# L-Stick_sheet5_power_supply.net
KiCad netlist of a schematic drawn in Altium Designer
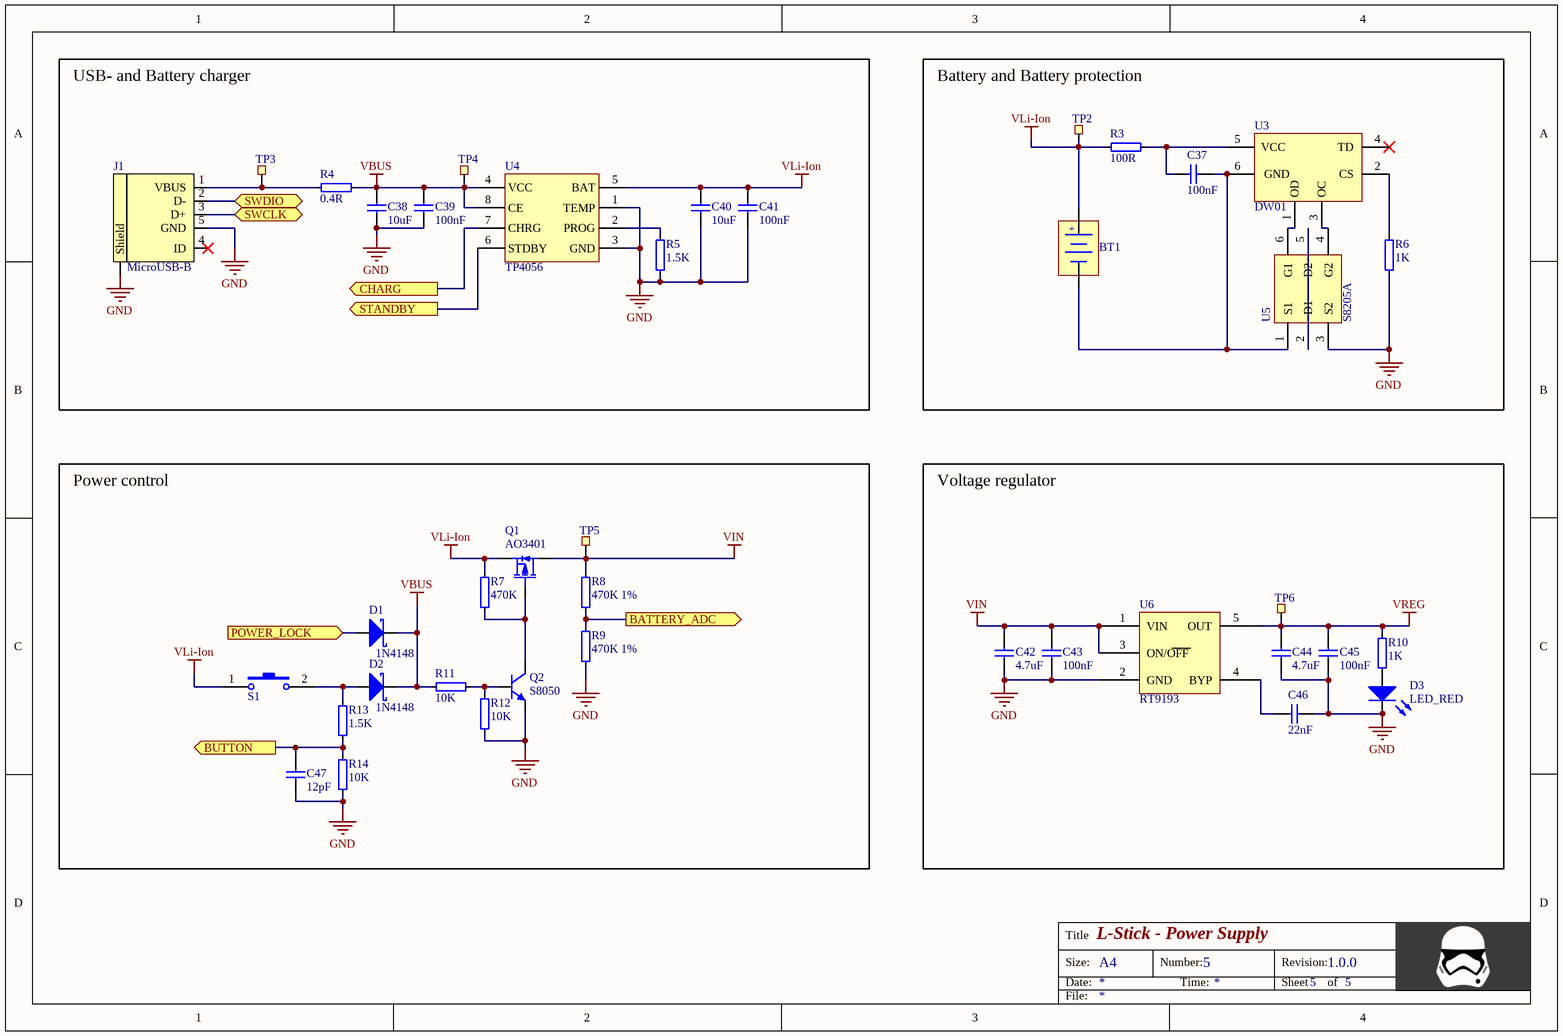
[diagram p0: L-Stick_sheet5_power_supply.SchDoc]

(export (version "E")
  (design (tool "Eeschema 10.0.6"))
  (components
    (comp (ref "BT1")
      (value "XH2.54_2PIN")
      (footprint "XH2.54_2PIN")
      (description "Multicell Battery Base")
      (libsource (lib "L-Stick") (part "Battery"))
    )
    (comp (ref "C37")
      (value "100nF")
      (footprint "0402C")
      (description "Capacitor")
      (libsource (lib "L-Stick") (part "CAP_0402"))
    )
    (comp (ref "C38")
      (value "10uF")
      (footprint "0603C")
      (description "Capacitor")
      (libsource (lib "L-Stick") (part "CAP_0603"))
    )
    (comp (ref "C39")
      (value "100nF")
      (footprint "0402C")
      (description "Capacitor")
      (libsource (lib "L-Stick") (part "CAP_0402"))
    )
    (comp (ref "C40")
      (value "10uF")
      (footprint "0603C")
      (description "Capacitor")
      (libsource (lib "L-Stick") (part "CAP_0603"))
    )
    (comp (ref "C41")
      (value "100nF")
      (footprint "0402C")
      (description "Capacitor")
      (libsource (lib "L-Stick") (part "CAP_0402"))
    )
    (comp (ref "C42")
      (value "4.7uF")
      (footprint "0603C")
      (description "Capacitor")
      (libsource (lib "L-Stick") (part "CAP_0603"))
    )
    (comp (ref "C43")
      (value "100nF")
      (footprint "0402C")
      (description "Capacitor")
      (libsource (lib "L-Stick") (part "CAP_0402"))
    )
    (comp (ref "C44")
      (value "4.7uF")
      (footprint "0603C")
      (description "Capacitor")
      (libsource (lib "L-Stick") (part "CAP_0603"))
    )
    (comp (ref "C45")
      (value "100nF")
      (footprint "0402C")
      (description "Capacitor")
      (libsource (lib "L-Stick") (part "CAP_0402"))
    )
    (comp (ref "C46")
      (value "22nF")
      (footprint "0402C")
      (description "Capacitor")
      (libsource (lib "L-Stick") (part "CAP_0402"))
    )
    (comp (ref "C47")
      (value "12pF")
      (footprint "0402C")
      (description "Capacitor")
      (libsource (lib "L-Stick") (part "CAP_0402"))
    )
    (comp (ref "D1")
      (value "1N4148")
      (footprint "SOD-523")
      (description "Diode Schottky")
      (libsource (lib "L-Stick") (part "Diode Schottky"))
    )
    (comp (ref "D2")
      (value "1N4148")
      (footprint "SOD-523")
      (description "Diode Schottky")
      (libsource (lib "L-Stick") (part "Diode Schottky"))
    )
    (comp (ref "D3")
      (value "LED_RED")
      (footprint "LED_RED_0603")
      (libsource (lib "L-Stick") (part "LED_RED"))
    )
    (comp (ref "J1")
      (value "MicroUSB-B")
      (footprint "USB-Micro")
      (description "MicroUSB-B-SMT")
      (libsource (lib "L-Stick") (part "MiniUSB-AB-SMT"))
    )
    (comp (ref "Q1")
      (value "AO3401")
      (footprint "SOT-23A")
      (description "P-MOS, AO3401, P-Channel MOSFET")
      (libsource (lib "L-Stick") (part "MOSFET-P"))
    )
    (comp (ref "Q2")
      (value "S8050")
      (footprint "SOT-23A")
      (description "NPN, S8050, NPN Bipolar Transistor")
      (libsource (lib "L-Stick") (part "NPN"))
    )
    (comp (ref "R3")
      (value "100R")
      (footprint "0402R")
      (description "Resistor")
      (libsource (lib "L-Stick") (part "RES_0402"))
    )
    (comp (ref "R4")
      (value "0.4R")
      (footprint "1206R")
      (description "Resistor")
      (libsource (lib "L-Stick") (part "RES_1206"))
    )
    (comp (ref "R5")
      (value "1.5K")
      (footprint "0402R")
      (description "Resistor")
      (libsource (lib "L-Stick") (part "RES_0402"))
    )
    (comp (ref "R6")
      (value "1K")
      (footprint "0402R")
      (description "Resistor")
      (libsource (lib "L-Stick") (part "RES_0402"))
    )
    (comp (ref "R7")
      (value "470K")
      (footprint "0402R")
      (description "Resistor")
      (libsource (lib "L-Stick") (part "RES_0402"))
    )
    (comp (ref "R8")
      (value "470K 1%")
      (footprint "0402R")
      (description "Resistor")
      (libsource (lib "L-Stick") (part "RES_0402"))
    )
    (comp (ref "R9")
      (value "470K 1%")
      (footprint "0402R")
      (description "Resistor")
      (libsource (lib "L-Stick") (part "RES_0402"))
    )
    (comp (ref "R10")
      (value "1K")
      (footprint "0402R")
      (description "Resistor")
      (libsource (lib "L-Stick") (part "RES_0402"))
    )
    (comp (ref "R11")
      (value "10K")
      (footprint "0402R")
      (description "Resistor")
      (libsource (lib "L-Stick") (part "RES_0402"))
    )
    (comp (ref "R12")
      (value "10K")
      (footprint "0402R")
      (description "Resistor")
      (libsource (lib "L-Stick") (part "RES_0402"))
    )
    (comp (ref "R13")
      (value "1.5K")
      (footprint "0402R")
      (description "Resistor")
      (libsource (lib "L-Stick") (part "RES_0402"))
    )
    (comp (ref "R14")
      (value "10K")
      (footprint "0402R")
      (description "Resistor")
      (libsource (lib "L-Stick") (part "RES_0402"))
    )
    (comp (ref "S1") (value "Side Button") (footprint "SW_SIDE") (libsource (lib "L-Stick") (part "SW-PB")))
    (comp (ref "TP2")
      (value "Ø1.5mm,SMD")
      (footprint "TP_SMD")
      (description "1.0mm circular SMD testpad")
      (libsource (lib "L-Stick") (part "TP_SMD_Ø1.0MM"))
    )
    (comp (ref "TP3")
      (value "Ø1.5mm,SMD")
      (footprint "TP_SMD")
      (description "1.0mm circular SMD testpad")
      (libsource (lib "L-Stick") (part "TP_SMD_Ø1.0MM"))
    )
    (comp (ref "TP4")
      (value "Ø1.5mm,SMD")
      (footprint "TP_SMD")
      (description "1.0mm circular SMD testpad")
      (libsource (lib "L-Stick") (part "TP_SMD_Ø1.0MM"))
    )
    (comp (ref "TP5")
      (value "Ø1.5mm,SMD")
      (footprint "TP_SMD")
      (description "1.0mm circular SMD testpad")
      (libsource (lib "L-Stick") (part "TP_SMD_Ø1.0MM"))
    )
    (comp (ref "TP6")
      (value "Ø1.5mm,SMD")
      (footprint "TP_SMD")
      (description "1.0mm circular SMD testpad")
      (libsource (lib "L-Stick") (part "TP_SMD_Ø1.0MM"))
    )
    (comp (ref "U3")
      (value "DW01")
      (footprint "SOT23-6")
      (description "Chip, DW01, Battery Protection IC")
      (libsource (lib "L-Stick") (part "DW01"))
    )
    (comp (ref "U4")
      (value "TP4056")
      (footprint "SOIC8E")
      (description "Chip, TP4056, Battery charging chip")
      (libsource (lib "L-Stick") (part "TP4056"))
    )
    (comp (ref "U5")
      (value "S8205A")
      (footprint "SOT23-6")
      (description "Chip, S8205A")
      (libsource (lib "L-Stick") (part "S8205A"))
    )
    (comp (ref "U6")
      (value "RT9193")
      (footprint "SOT23-5")
      (description "Chip, RT9193, LDO Regulator")
      (libsource (lib "L-Stick") (part "RT9193"))
    )
  )
  (nets
    (net (code "1") (name "/BATTERY_ADC") (class "Default")
      (node (ref "R8") (pin "2") (pinfunction "2_2") (pintype "passive"))
      (node (ref "R9") (pin "1") (pinfunction "1_1") (pintype "passive"))
    )
    (net (code "2") (name "/BUTTON") (class "Default")
      (node (ref "C47") (pin "2") (pinfunction "2_2") (pintype "passive"))
      (node (ref "R13") (pin "1") (pinfunction "1_1") (pintype "passive"))
      (node (ref "R14") (pin "2") (pinfunction "2_2") (pintype "passive"))
    )
    (net (code "3") (name "/CHARG") (class "Default")
      (node (ref "U4") (pin "7") (pinfunction "CHRG_7") (pintype "passive"))
    )
    (net (code "4") (name "/POWER_LOCK") (class "Default")
      (node (ref "D1") (pin "1") (pinfunction "A_1") (pintype "passive"))
    )
    (net (code "5") (name "/STANDBY") (class "Default")
      (node (ref "U4") (pin "6") (pinfunction "STDBY_6") (pintype "passive"))
    )
    (net (code "6") (name "/SWCLK") (class "Default")
      (node (ref "J1") (pin "3") (pinfunction "D+_3") (pintype "passive"))
    )
    (net (code "7") (name "/SWDIO") (class "Default")
      (node (ref "J1") (pin "2") (pinfunction "D-_2") (pintype "passive"))
    )
    (net (code "8") (name "GND") (class "Default")
      (node (ref "C38") (pin "1") (pinfunction "1_1") (pintype "passive"))
      (node (ref "C39") (pin "1") (pinfunction "1_1") (pintype "passive"))
      (node (ref "C40") (pin "1") (pinfunction "1_1") (pintype "passive"))
      (node (ref "C41") (pin "1") (pinfunction "1_1") (pintype "passive"))
      (node (ref "C42") (pin "1") (pinfunction "1_1") (pintype "passive"))
      (node (ref "C43") (pin "1") (pinfunction "1_1") (pintype "passive"))
      (node (ref "C44") (pin "1") (pinfunction "1_1") (pintype "passive"))
      (node (ref "C45") (pin "1") (pinfunction "1_1") (pintype "passive"))
      (node (ref "C46") (pin "2") (pinfunction "2_2") (pintype "passive"))
      (node (ref "C47") (pin "1") (pinfunction "1_1") (pintype "passive"))
      (node (ref "D3") (pin "2") (pinfunction "K_2") (pintype "passive"))
      (node (ref "J1") (pin "5") (pinfunction "GND_5") (pintype "power_in"))
      (node (ref "J1") (pin "6") (pinfunction "Shield_6") (pintype "power_in"))
      (node (ref "Q2") (pin "2") (pinfunction "E_2") (pintype "passive"))
      (node (ref "R12") (pin "2") (pinfunction "2_2") (pintype "passive"))
      (node (ref "R14") (pin "1") (pinfunction "1_1") (pintype "passive"))
      (node (ref "R5") (pin "1") (pinfunction "1_1") (pintype "passive"))
      (node (ref "R6") (pin "1") (pinfunction "1_1") (pintype "passive"))
      (node (ref "R9") (pin "2") (pinfunction "2_2") (pintype "passive"))
      (node (ref "U4") (pin "1") (pinfunction "TEMP_1") (pintype "passive"))
      (node (ref "U4") (pin "3") (pinfunction "GND_3") (pintype "passive"))
      (node (ref "U5") (pin "3") (pinfunction "S2_3") (pintype "passive"))
      (node (ref "U6") (pin "2") (pinfunction "GND_2") (pintype "passive"))
    )
    (net (code "9") (name "Net-(BT1--)") (class "Default")
      (node (ref "BT1") (pin "2") (pinfunction "-_2") (pintype "passive"))
      (node (ref "C37") (pin "2") (pinfunction "2_2") (pintype "passive"))
      (node (ref "U3") (pin "6") (pinfunction "GND_6") (pintype "passive"))
      (node (ref "U5") (pin "1") (pinfunction "S1_1") (pintype "passive"))
    )
    (net (code "10") (name "Net-(D2-A)") (class "Default")
      (node (ref "D2") (pin "1") (pinfunction "A_1") (pintype "passive"))
      (node (ref "R13") (pin "2") (pinfunction "2_2") (pintype "passive"))
      (node (ref "S1") (pin "2") (pinfunction "2_2") (pintype "passive"))
    )
    (net (code "11") (name "Net-(D3-A)") (class "Default")
      (node (ref "D3") (pin "1") (pinfunction "A_1") (pintype "passive"))
      (node (ref "R10") (pin "1") (pinfunction "1_1") (pintype "passive"))
    )
    (net (code "12") (name "Net-(J1-VBUS)") (class "Default")
      (node (ref "J1") (pin "1") (pinfunction "VBUS_1") (pintype "power_in"))
      (node (ref "R4") (pin "1") (pinfunction "1_1") (pintype "passive"))
      (node (ref "TP3") (pin "1") (pinfunction "1_1") (pintype "passive"))
    )
    (net (code "13") (name "Net-(Q1-G)") (class "Default")
      (node (ref "Q1") (pin "1") (pinfunction "G_1") (pintype "passive"))
      (node (ref "Q2") (pin "3") (pinfunction "C_3") (pintype "passive"))
      (node (ref "R7") (pin "2") (pinfunction "2_2") (pintype "passive"))
    )
    (net (code "14") (name "Net-(Q2-B)") (class "Default")
      (node (ref "Q2") (pin "1") (pinfunction "B_1") (pintype "passive"))
      (node (ref "R11") (pin "1") (pinfunction "1_1") (pintype "passive"))
      (node (ref "R12") (pin "1") (pinfunction "1_1") (pintype "passive"))
    )
    (net (code "15") (name "Net-(U3-CS)") (class "Default")
      (node (ref "R6") (pin "2") (pinfunction "2_2") (pintype "passive"))
      (node (ref "U3") (pin "2") (pinfunction "CS_2") (pintype "passive"))
    )
    (net (code "16") (name "Net-(U3-OC)") (class "Default")
      (node (ref "U3") (pin "3") (pinfunction "OC_3") (pintype "passive"))
      (node (ref "U5") (pin "4") (pinfunction "G2_4") (pintype "passive"))
    )
    (net (code "17") (name "Net-(U3-OD)") (class "Default")
      (node (ref "U3") (pin "1") (pinfunction "OD_1") (pintype "passive"))
      (node (ref "U5") (pin "6") (pinfunction "G1_6") (pintype "passive"))
    )
    (net (code "18") (name "Net-(U3-VCC)") (class "Default")
      (node (ref "C37") (pin "1") (pinfunction "1_1") (pintype "passive"))
      (node (ref "R3") (pin "2") (pinfunction "2_2") (pintype "passive"))
      (node (ref "U3") (pin "5") (pinfunction "VCC_5") (pintype "passive"))
    )
    (net (code "19") (name "Net-(U4-PROG)") (class "Default")
      (node (ref "R5") (pin "2") (pinfunction "2_2") (pintype "passive"))
      (node (ref "U4") (pin "2") (pinfunction "PROG_2") (pintype "passive"))
    )
    (net (code "20") (name "Net-(U5-D1)") (class "Default")
      (node (ref "U5") (pin "2") (pinfunction "D1_2") (pintype "passive"))
      (node (ref "U5") (pin "5") (pinfunction "D2_5") (pintype "passive"))
    )
    (net (code "21") (name "Net-(U6-BYP)") (class "Default")
      (node (ref "C46") (pin "1") (pinfunction "1_1") (pintype "passive"))
      (node (ref "U6") (pin "4") (pinfunction "BYP_4") (pintype "passive"))
    )
    (net (code "22") (name "VBUS") (class "Default")
      (node (ref "C38") (pin "2") (pinfunction "2_2") (pintype "passive"))
      (node (ref "C39") (pin "2") (pinfunction "2_2") (pintype "passive"))
      (node (ref "D1") (pin "2") (pinfunction "K_2") (pintype "passive"))
      (node (ref "D2") (pin "2") (pinfunction "K_2") (pintype "passive"))
      (node (ref "R11") (pin "2") (pinfunction "2_2") (pintype "passive"))
      (node (ref "R4") (pin "2") (pinfunction "2_2") (pintype "passive"))
      (node (ref "TP4") (pin "1") (pinfunction "1_1") (pintype "passive"))
      (node (ref "U4") (pin "4") (pinfunction "VCC_4") (pintype "passive"))
      (node (ref "U4") (pin "8") (pinfunction "CE_8") (pintype "passive"))
    )
    (net (code "23") (name "VIN") (class "Default")
      (node (ref "C42") (pin "2") (pinfunction "2_2") (pintype "passive"))
      (node (ref "C43") (pin "2") (pinfunction "2_2") (pintype "passive"))
      (node (ref "Q1") (pin "3") (pinfunction "D_3") (pintype "passive"))
      (node (ref "R8") (pin "1") (pinfunction "1_1") (pintype "passive"))
      (node (ref "TP5") (pin "1") (pinfunction "1_1") (pintype "passive"))
      (node (ref "U6") (pin "1") (pinfunction "VIN_1") (pintype "passive"))
      (node (ref "U6") (pin "3") (pinfunction "ON/OFF_3") (pintype "passive"))
    )
    (net (code "24") (name "VLi-Ion") (class "Default")
      (node (ref "BT1") (pin "1") (pinfunction "+_1") (pintype "passive"))
      (node (ref "C40") (pin "2") (pinfunction "2_2") (pintype "passive"))
      (node (ref "C41") (pin "2") (pinfunction "2_2") (pintype "passive"))
      (node (ref "Q1") (pin "2") (pinfunction "S_2") (pintype "passive"))
      (node (ref "R3") (pin "1") (pinfunction "1_1") (pintype "passive"))
      (node (ref "R7") (pin "1") (pinfunction "1_1") (pintype "passive"))
      (node (ref "S1") (pin "1") (pinfunction "1_1") (pintype "passive"))
      (node (ref "TP2") (pin "1") (pinfunction "1_1") (pintype "passive"))
      (node (ref "U4") (pin "5") (pinfunction "BAT_5") (pintype "passive"))
    )
    (net (code "25") (name "VREG") (class "Default")
      (node (ref "C44") (pin "2") (pinfunction "2_2") (pintype "passive"))
      (node (ref "C45") (pin "2") (pinfunction "2_2") (pintype "passive"))
      (node (ref "R10") (pin "2") (pinfunction "2_2") (pintype "passive"))
      (node (ref "TP6") (pin "1") (pinfunction "1_1") (pintype "passive"))
      (node (ref "U6") (pin "5") (pinfunction "OUT_5") (pintype "passive"))
    )
    (net (code "26") (name "unconnected-(J1-ID-Pad4)") (class "Default")
      (node (ref "J1") (pin "4") (pinfunction "ID_4") (pintype "passive+no_connect"))
    )
    (net (code "27") (name "unconnected-(U3-TD-Pad4)") (class "Default")
      (node (ref "U3") (pin "4") (pinfunction "TD_4") (pintype "passive+no_connect"))
    )
  )
)
